# Ds3231Shield.net
KiCad netlist of a schematic drawn in EAGLE
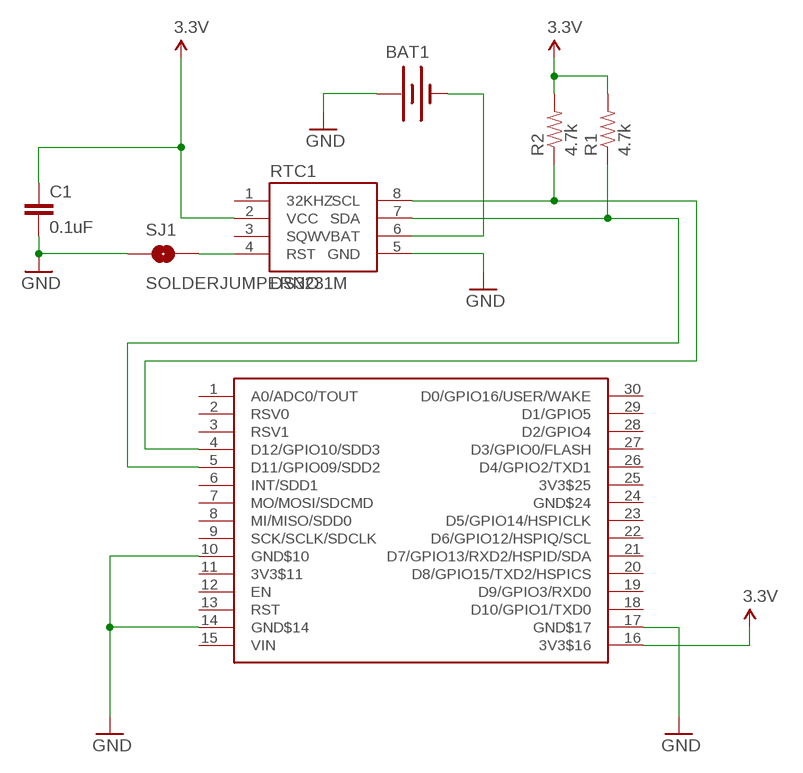
[diagram p0: schematic, sheet 1]

(export (version "E")
  (design (tool "Eeschema 10.0.6"))
  (components
    (comp (ref "BAT1")
      (value "BATTERY12MM")
      (footprint "eagle-import:BATTCON_12MM")
      (libsource (lib "eagle-import") (part "BATTERY12MM"))
    )
    (comp (ref "C1")
      (value "0.1uF")
      (footprint "eagle-import:0402-CAP")
      (libsource (lib "eagle-import") (part "CAP0402-CAP"))
    )
    (comp (ref "R1")
      (value "4.7k")
      (footprint "eagle-import:0402-RES")
      (libsource (lib "eagle-import") (part "RESISTOR0402-RES"))
    )
    (comp (ref "R2")
      (value "4.7k")
      (footprint "eagle-import:0402-RES")
      (libsource (lib "eagle-import") (part "RESISTOR0402-RES"))
    )
    (comp (ref "RTC1")
      (value "DS3231M")
      (footprint "eagle-import:SOIC8")
      (libsource (lib "eagle-import") (part "DS3231M"))
    )
    (comp (ref "SJ1")
      (value "SOLDERJUMPERNO")
      (footprint "eagle-import:SJ_2S-NO")
      (libsource (lib "eagle-import") (part "SOLDERJUMPERNO"))
    )
    (comp (ref "U$1")
      (value "NERDSHIELD")
      (footprint "eagle-import:NERDUINO_STACK")
      (libsource (lib "eagle-import") (part "NERDSHIELD"))
    )
  )
  (nets
    (net (code "1") (name "3.3V") (class "Default")
      (node (ref "C1") (pin "1") (pinfunction "1_1") (pintype "passive"))
      (node (ref "R1") (pin "2") (pinfunction "2_2") (pintype "passive"))
      (node (ref "R2") (pin "2") (pinfunction "2_2") (pintype "passive"))
      (node (ref "RTC1") (pin "2") (pinfunction "VCC_2") (pintype "power_in"))
      (node (ref "U$1") (pin "16") (pinfunction "3V3$16_16") (pintype "bidirectional"))
    )
    (net (code "2") (name "GND") (class "Default")
      (node (ref "BAT1") (pin "PWR@1") (pinfunction "+_PWR@1") (pintype "power_in"))
      (node (ref "C1") (pin "2") (pinfunction "2_2") (pintype "passive"))
      (node (ref "RTC1") (pin "5") (pinfunction "GND_5") (pintype "power_in"))
      (node (ref "SJ1") (pin "1") (pinfunction "1_1") (pintype "passive"))
      (node (ref "U$1") (pin "10") (pinfunction "GND$10_10") (pintype "bidirectional"))
      (node (ref "U$1") (pin "14") (pinfunction "GND$14_14") (pintype "bidirectional"))
      (node (ref "U$1") (pin "17") (pinfunction "GND$17_17") (pintype "bidirectional"))
    )
    (net (code "3") (name "Net-(BAT1--)") (class "Default")
      (node (ref "BAT1") (pin "GND") (pinfunction "-_GND") (pintype "power_in"))
      (node (ref "RTC1") (pin "6") (pinfunction "VBAT_6") (pintype "power_in"))
    )
    (net (code "4") (name "Net-(RTC1-RST)") (class "Default")
      (node (ref "RTC1") (pin "4") (pinfunction "RST_4") (pintype "bidirectional"))
      (node (ref "SJ1") (pin "2") (pinfunction "2_2") (pintype "passive"))
    )
    (net (code "5") (name "Net-(RTC1-SCL)") (class "Default")
      (node (ref "R2") (pin "1") (pinfunction "1_1") (pintype "passive"))
      (node (ref "RTC1") (pin "8") (pinfunction "SCL_8") (pintype "bidirectional"))
      (node (ref "U$1") (pin "4") (pinfunction "D12/GPIO10/SDD3_4") (pintype "bidirectional"))
    )
    (net (code "6") (name "Net-(RTC1-SDA)") (class "Default")
      (node (ref "R1") (pin "1") (pinfunction "1_1") (pintype "passive"))
      (node (ref "RTC1") (pin "7") (pinfunction "SDA_7") (pintype "bidirectional"))
      (node (ref "U$1") (pin "5") (pinfunction "D11/GPIO09/SDD2_5") (pintype "bidirectional"))
    )
    (net (code "7") (name "unconnected-(RTC1-32KHZ-Pad1)") (class "Default")
      (node (ref "RTC1") (pin "1") (pinfunction "32KHZ_1") (pintype "output"))
    )
    (net (code "8") (name "unconnected-(RTC1-SQW-Pad3)") (class "Default")
      (node (ref "RTC1") (pin "3") (pinfunction "SQW_3") (pintype "output"))
    )
    (net (code "9") (name "unconnected-(U$1-3V3$11-Pad11)") (class "Default")
      (node (ref "U$1") (pin "11") (pinfunction "3V3$11_11") (pintype "bidirectional"))
    )
    (net (code "10") (name "unconnected-(U$1-3V3$25-Pad25)") (class "Default")
      (node (ref "U$1") (pin "25") (pinfunction "3V3$25_25") (pintype "bidirectional"))
    )
    (net (code "11") (name "unconnected-(U$1-A0{slash}ADC0{slash}TOUT-Pad1)") (class "Default")
      (node (ref "U$1") (pin "1") (pinfunction "A0/ADC0/TOUT_1") (pintype "bidirectional"))
    )
    (net (code "12") (name "unconnected-(U$1-D0{slash}GPIO16{slash}USER{slash}WAKE-Pad30)") (class "Default")
      (node (ref "U$1") (pin "30") (pinfunction "D0/GPIO16/USER/WAKE_30") (pintype "bidirectional"))
    )
    (net (code "13") (name "unconnected-(U$1-D1{slash}GPIO5-Pad29)") (class "Default")
      (node (ref "U$1") (pin "29") (pinfunction "D1/GPIO5_29") (pintype "bidirectional"))
    )
    (net (code "14") (name "unconnected-(U$1-D2{slash}GPIO4-Pad28)") (class "Default")
      (node (ref "U$1") (pin "28") (pinfunction "D2/GPIO4_28") (pintype "bidirectional"))
    )
    (net (code "15") (name "unconnected-(U$1-D3{slash}GPIO0{slash}FLASH-Pad27)") (class "Default")
      (node (ref "U$1") (pin "27") (pinfunction "D3/GPIO0/FLASH_27") (pintype "bidirectional"))
    )
    (net (code "16") (name "unconnected-(U$1-D4{slash}GPIO2{slash}TXD1-Pad26)") (class "Default")
      (node (ref "U$1") (pin "26") (pinfunction "D4/GPIO2/TXD1_26") (pintype "bidirectional"))
    )
    (net (code "17") (name "unconnected-(U$1-D5{slash}GPIO14{slash}HSPICLK-Pad23)") (class "Default")
      (node (ref "U$1") (pin "23") (pinfunction "D5/GPIO14/HSPICLK_23") (pintype "bidirectional"))
    )
    (net (code "18") (name "unconnected-(U$1-D6{slash}GPIO12{slash}HSPIQ{slash}SCL-Pad22)") (class "Default")
      (node (ref "U$1") (pin "22") (pinfunction "D6/GPIO12/HSPIQ/SCL_22") (pintype "bidirectional"))
    )
    (net (code "19") (name "unconnected-(U$1-D7{slash}GPIO13{slash}RXD2{slash}HSPID{slash}SDA-Pad21)") (class "Default")
      (node (ref "U$1") (pin "21") (pinfunction "D7/GPIO13/RXD2/HSPID/SDA_21") (pintype "bidirectional"))
    )
    (net (code "20") (name "unconnected-(U$1-D8{slash}GPIO15{slash}TXD2{slash}HSPICS-Pad20)") (class "Default")
      (node (ref "U$1") (pin "20") (pinfunction "D8/GPIO15/TXD2/HSPICS_20") (pintype "bidirectional"))
    )
    (net (code "21") (name "unconnected-(U$1-D9{slash}GPIO3{slash}RXD0-Pad19)") (class "Default")
      (node (ref "U$1") (pin "19") (pinfunction "D9/GPIO3/RXD0_19") (pintype "bidirectional"))
    )
    (net (code "22") (name "unconnected-(U$1-D10{slash}GPIO1{slash}TXD0-Pad18)") (class "Default")
      (node (ref "U$1") (pin "18") (pinfunction "D10/GPIO1/TXD0_18") (pintype "bidirectional"))
    )
    (net (code "23") (name "unconnected-(U$1-EN-Pad12)") (class "Default")
      (node (ref "U$1") (pin "12") (pinfunction "EN_12") (pintype "bidirectional"))
    )
    (net (code "24") (name "unconnected-(U$1-GND$24-Pad24)") (class "Default")
      (node (ref "U$1") (pin "24") (pinfunction "GND$24_24") (pintype "bidirectional"))
    )
    (net (code "25") (name "unconnected-(U$1-INT{slash}SDD1-Pad6)") (class "Default")
      (node (ref "U$1") (pin "6") (pinfunction "INT/SDD1_6") (pintype "bidirectional"))
    )
    (net (code "26") (name "unconnected-(U$1-MI{slash}MISO{slash}SDD0-Pad8)") (class "Default")
      (node (ref "U$1") (pin "8") (pinfunction "MI/MISO/SDD0_8") (pintype "bidirectional"))
    )
    (net (code "27") (name "unconnected-(U$1-MO{slash}MOSI{slash}SDCMD-Pad7)") (class "Default")
      (node (ref "U$1") (pin "7") (pinfunction "MO/MOSI/SDCMD_7") (pintype "bidirectional"))
    )
    (net (code "28") (name "unconnected-(U$1-RST-Pad13)") (class "Default")
      (node (ref "U$1") (pin "13") (pinfunction "RST_13") (pintype "bidirectional"))
    )
    (net (code "29") (name "unconnected-(U$1-RSV0-Pad2)") (class "Default")
      (node (ref "U$1") (pin "2") (pinfunction "RSV0_2") (pintype "bidirectional"))
    )
    (net (code "30") (name "unconnected-(U$1-RSV1-Pad3)") (class "Default")
      (node (ref "U$1") (pin "3") (pinfunction "RSV1_3") (pintype "bidirectional"))
    )
    (net (code "31") (name "unconnected-(U$1-SCK{slash}SCLK{slash}SDCLK-Pad9)") (class "Default")
      (node (ref "U$1") (pin "9") (pinfunction "SCK/SCLK/SDCLK_9") (pintype "bidirectional"))
    )
    (net (code "32") (name "unconnected-(U$1-VIN-Pad15)") (class "Default")
      (node (ref "U$1") (pin "15") (pinfunction "VIN_15") (pintype "bidirectional"))
    )
  )
)
